# breadboard_rev06.net
KiCad netlist of a schematic drawn in EAGLE
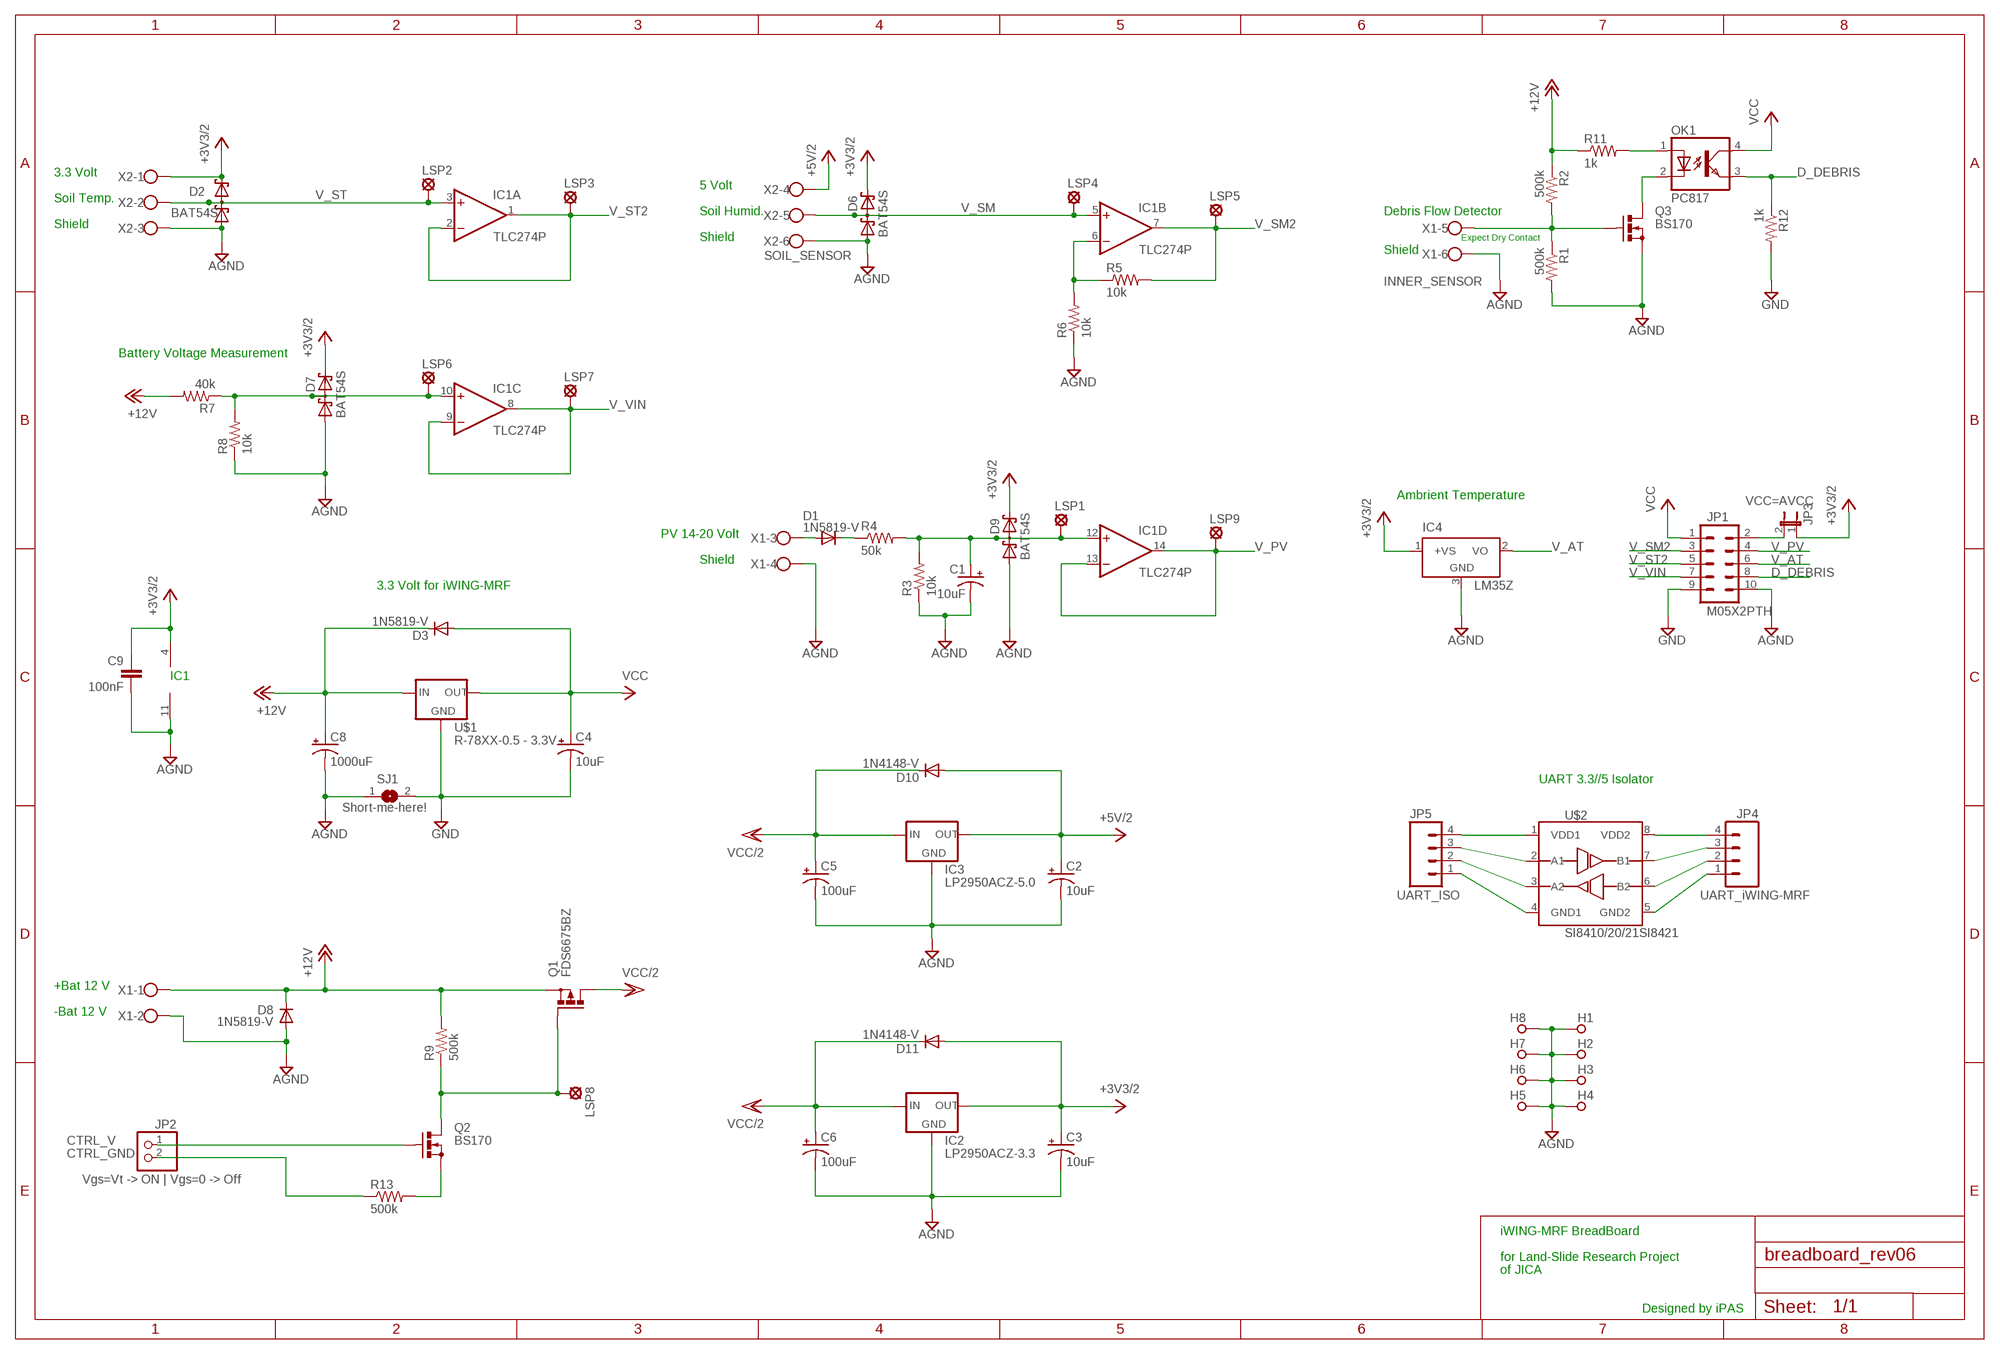
[diagram p0: schematic, sheet 1]

(export (version "E")
  (design (tool "Eeschema 10.0.6"))
  (components
    (comp (ref "C1")
      (value "10uF")
      (footprint "eagle-import:RCL_E2,5-7")
      (libsource (lib "eagle-import") (part "RCL_CPOL-USE2.5-7"))
    )
    (comp (ref "C2")
      (value "10uF")
      (footprint "eagle-import:RCL_E2,5-7")
      (libsource (lib "eagle-import") (part "RCL_CPOL-USE2.5-7"))
    )
    (comp (ref "C3")
      (value "10uF")
      (footprint "eagle-import:RCL_E2,5-7")
      (libsource (lib "eagle-import") (part "RCL_CPOL-USE2.5-7"))
    )
    (comp (ref "C4")
      (value "10uF")
      (footprint "eagle-import:RCL_E2,5-7")
      (libsource (lib "eagle-import") (part "RCL_CPOL-USE2.5-7"))
    )
    (comp (ref "C5")
      (value "100uF")
      (footprint "eagle-import:RCL_E2,5-7")
      (libsource (lib "eagle-import") (part "RCL_CPOL-USE2.5-7"))
    )
    (comp (ref "C6")
      (value "100uF")
      (footprint "eagle-import:RCL_E2,5-7")
      (libsource (lib "eagle-import") (part "RCL_CPOL-USE2.5-7"))
    )
    (comp (ref "C8")
      (value "1000uF")
      (footprint "eagle-import:RCL_E5-13")
      (libsource (lib "eagle-import") (part "RCL_CPOL-USE5-13"))
    )
    (comp (ref "C9")
      (value "100nF")
      (footprint "eagle-import:RCL_C050-025X075")
      (libsource (lib "eagle-import") (part "RCL_C-EU050-025X075"))
    )
    (comp (ref "D1")
      (value "1N5819-V")
      (footprint "eagle-import:DO41-150V")
      (libsource (lib "eagle-import") (part "1N5819-V"))
    )
    (comp (ref "D2")
      (value "BAT54S")
      (footprint "eagle-import:SOT23")
      (libsource (lib "eagle-import") (part "BAT54S"))
    )
    (comp (ref "D3")
      (value "1N5819-V")
      (footprint "eagle-import:DO41-150V")
      (libsource (lib "eagle-import") (part "1N5819-V"))
    )
    (comp (ref "D6")
      (value "BAT54S")
      (footprint "eagle-import:SOT23")
      (libsource (lib "eagle-import") (part "BAT54S"))
    )
    (comp (ref "D7")
      (value "BAT54S")
      (footprint "eagle-import:SOT23")
      (libsource (lib "eagle-import") (part "BAT54S"))
    )
    (comp (ref "D8")
      (value "1N5819-V")
      (footprint "eagle-import:DO41-150V")
      (libsource (lib "eagle-import") (part "1N5819-V"))
    )
    (comp (ref "D9")
      (value "BAT54S")
      (footprint "eagle-import:SOT23")
      (libsource (lib "eagle-import") (part "BAT54S"))
    )
    (comp (ref "D10")
      (value "1N4148-V")
      (footprint "eagle-import:DO35-100V")
      (libsource (lib "eagle-import") (part "1N4148-V"))
    )
    (comp (ref "D11")
      (value "1N4148-V")
      (footprint "eagle-import:DO35-100V")
      (libsource (lib "eagle-import") (part "1N4148-V"))
    )
    (comp (ref "H1")
      (value "SPECIAL_DRILL_0.1560")
      (footprint "eagle-import:PAD_0.1560")
      (libsource (lib "eagle-import") (part "SPECIAL_DRILL_0.1560"))
    )
    (comp (ref "H2")
      (value "SPECIAL_DRILL_0.1560")
      (footprint "eagle-import:PAD_0.1560")
      (libsource (lib "eagle-import") (part "SPECIAL_DRILL_0.1560"))
    )
    (comp (ref "H3")
      (value "SPECIAL_DRILL_0.1560")
      (footprint "eagle-import:PAD_0.1560")
      (libsource (lib "eagle-import") (part "SPECIAL_DRILL_0.1560"))
    )
    (comp (ref "H4")
      (value "SPECIAL_DRILL_0.1560")
      (footprint "eagle-import:PAD_0.1560")
      (libsource (lib "eagle-import") (part "SPECIAL_DRILL_0.1560"))
    )
    (comp (ref "H5")
      (value "SPECIAL_DRILL_0.1560")
      (footprint "eagle-import:PAD_0.1560")
      (libsource (lib "eagle-import") (part "SPECIAL_DRILL_0.1560"))
    )
    (comp (ref "H6")
      (value "SPECIAL_DRILL_0.1560")
      (footprint "eagle-import:PAD_0.1560")
      (libsource (lib "eagle-import") (part "SPECIAL_DRILL_0.1560"))
    )
    (comp (ref "H7")
      (value "SPECIAL_DRILL_0.1560")
      (footprint "eagle-import:PAD_0.1560")
      (libsource (lib "eagle-import") (part "SPECIAL_DRILL_0.1560"))
    )
    (comp (ref "H8")
      (value "SPECIAL_DRILL_0.1560")
      (footprint "eagle-import:PAD_0.1560")
      (libsource (lib "eagle-import") (part "SPECIAL_DRILL_0.1560"))
    )
    (comp (ref "IC1")
      (value "TLC274P")
      (footprint "eagle-import:DIL14")
      (libsource (lib "eagle-import") (part "TLC274P"))
    )
    (comp (ref "IC2")
      (value "LP2950ACZ-3.3")
      (footprint "eagle-import:TO92")
      (libsource (lib "eagle-import") (part "LP2950?ACZ-3.3"))
    )
    (comp (ref "IC3")
      (value "LP2950ACZ-5.0")
      (footprint "eagle-import:TO92")
      (libsource (lib "eagle-import") (part "LP2950?ACZ-5.0"))
    )
    (comp (ref "IC4")
      (value "LM35Z")
      (footprint "eagle-import:TO92")
      (libsource (lib "eagle-import") (part "LM35?Z"))
    )
    (comp (ref "JP1")
      (value "M05X2PTH")
      (footprint "eagle-import:AVR_ICSP")
      (libsource (lib "eagle-import") (part "M05X2PTH"))
    )
    (comp (ref "JP2")
      (value "Vgs=Vt -> ON | Vgs=0 -> Off")
      (footprint "eagle-import:1X02")
      (libsource (lib "eagle-import") (part "PINHD-1X2"))
    )
    (comp (ref "JP3")
      (value "VCC=AVCC")
      (footprint "eagle-import:JUMPER_JP1")
      (libsource (lib "eagle-import") (part "JP1E"))
    )
    (comp (ref "JP4")
      (value "UART_iWING-MRF")
      (footprint "eagle-import:MOLEX-1X4")
      (libsource (lib "eagle-import") (part "M04POLAR"))
    )
    (comp (ref "JP5")
      (value "UART_ISO")
      (footprint "eagle-import:MOLEX-1X4")
      (libsource (lib "eagle-import") (part "M04POLAR"))
    )
    (comp (ref "LSP1")
      (value "LSP13")
      (footprint "eagle-import:LSP13")
      (libsource (lib "eagle-import") (part "LSP13"))
    )
    (comp (ref "LSP2")
      (value "LSP13")
      (footprint "eagle-import:LSP13")
      (libsource (lib "eagle-import") (part "LSP13"))
    )
    (comp (ref "LSP3")
      (value "LSP13")
      (footprint "eagle-import:LSP13")
      (libsource (lib "eagle-import") (part "LSP13"))
    )
    (comp (ref "LSP4")
      (value "LSP13")
      (footprint "eagle-import:LSP13")
      (libsource (lib "eagle-import") (part "LSP13"))
    )
    (comp (ref "LSP5")
      (value "LSP13")
      (footprint "eagle-import:LSP13")
      (libsource (lib "eagle-import") (part "LSP13"))
    )
    (comp (ref "LSP6")
      (value "LSP13")
      (footprint "eagle-import:LSP13")
      (libsource (lib "eagle-import") (part "LSP13"))
    )
    (comp (ref "LSP7")
      (value "LSP13")
      (footprint "eagle-import:LSP13")
      (libsource (lib "eagle-import") (part "LSP13"))
    )
    (comp (ref "LSP8")
      (value "LSP13")
      (footprint "eagle-import:LSP13")
      (libsource (lib "eagle-import") (part "LSP13"))
    )
    (comp (ref "LSP9")
      (value "LSP13")
      (footprint "eagle-import:LSP13")
      (libsource (lib "eagle-import") (part "LSP13"))
    )
    (comp (ref "OK1")
      (value "PC817")
      (footprint "eagle-import:DIL04")
      (fields (field (name "MPN") "PC817X4J000F"))
      (libsource (lib "eagle-import") (part "PC817"))
    )
    (comp (ref "Q1")
      (value "FDS6675BZ")
      (footprint "eagle-import:SO-08")
      (libsource (lib "eagle-import") (part "P-MOSFET-SO8"))
    )
    (comp (ref "Q2")
      (value "BS170")
      (footprint "eagle-import:SOT54E")
      (libsource (lib "eagle-import") (part "BS170"))
    )
    (comp (ref "Q3")
      (value "BS170")
      (footprint "eagle-import:SOT54E")
      (libsource (lib "eagle-import") (part "BS170"))
    )
    (comp (ref "R1")
      (value "500k")
      (footprint "eagle-import:RCL_0204_7")
      (libsource (lib "eagle-import") (part "RCL_R-US_0204/7"))
    )
    (comp (ref "R2")
      (value "500k")
      (footprint "eagle-import:RCL_0204_7")
      (libsource (lib "eagle-import") (part "RCL_R-US_0204/7"))
    )
    (comp (ref "R3")
      (value "10k")
      (footprint "eagle-import:RCL_0204_7")
      (libsource (lib "eagle-import") (part "RCL_R-US_0204/7"))
    )
    (comp (ref "R4")
      (value "50k")
      (footprint "eagle-import:RCL_0204_7")
      (libsource (lib "eagle-import") (part "RCL_R-US_0204/7"))
    )
    (comp (ref "R5")
      (value "10k")
      (footprint "eagle-import:RCL_0204_7")
      (libsource (lib "eagle-import") (part "RCL_R-US_0204/7"))
    )
    (comp (ref "R6")
      (value "10k")
      (footprint "eagle-import:RCL_0204_7")
      (libsource (lib "eagle-import") (part "RCL_R-US_0204/7"))
    )
    (comp (ref "R7")
      (value "40k")
      (footprint "eagle-import:RCL_0204_7")
      (libsource (lib "eagle-import") (part "RCL_R-US_0204/7"))
    )
    (comp (ref "R8")
      (value "10k")
      (footprint "eagle-import:RCL_0204_7")
      (libsource (lib "eagle-import") (part "RCL_R-US_0204/7"))
    )
    (comp (ref "R9")
      (value "500k")
      (footprint "eagle-import:RCL_0204_7")
      (libsource (lib "eagle-import") (part "RCL_R-US_0204/7"))
    )
    (comp (ref "R11")
      (value "1k")
      (footprint "eagle-import:RCL_0204_7")
      (libsource (lib "eagle-import") (part "RCL_R-US_0204/7"))
    )
    (comp (ref "R12")
      (value "1k")
      (footprint "eagle-import:RCL_0204_7")
      (libsource (lib "eagle-import") (part "RCL_R-US_0204/7"))
    )
    (comp (ref "R13")
      (value "500k")
      (footprint "eagle-import:RCL_0204_7")
      (libsource (lib "eagle-import") (part "RCL_R-US_0204/7"))
    )
    (comp (ref "SJ1")
      (value "Short-me-here!")
      (footprint "eagle-import:SJ")
      (libsource (lib "eagle-import") (part "SJ"))
    )
    (comp (ref "U$1")
      (value "R-78XX-0.5 - 3.3V")
      (footprint "eagle-import:SIP3")
      (libsource (lib "eagle-import") (part "R-78XX-0.5"))
    )
    (comp (ref "U$2")
      (value "SI8410/20/21SI8421")
      (footprint "eagle-import:SO-08")
      (libsource (lib "eagle-import") (part "SI8410/20/21SI8421"))
    )
    (comp (ref "X1")
      (value "INNER_SENSOR")
      (footprint "eagle-import:5EHDRC-6P")
      (libsource (lib "eagle-import") (part "5EHDRC-6P"))
    )
    (comp (ref "X2")
      (value "SOIL_SENSOR")
      (footprint "eagle-import:5EHDRC-6P")
      (libsource (lib "eagle-import") (part "5EHDRC-6P"))
    )
  )
  (nets
    (net (code "1") (name "+3V3{slash}2") (class "Default")
      (node (ref "C3") (pin "+") (pinfunction "+_+") (pintype "passive"))
      (node (ref "C9") (pin "1") (pinfunction "1_1") (pintype "passive"))
      (node (ref "D11") (pin "A") (pinfunction "A_A") (pintype "passive"))
      (node (ref "D2") (pin "2") (pinfunction "C2_2") (pintype "passive"))
      (node (ref "D6") (pin "2") (pinfunction "C2_2") (pintype "passive"))
      (node (ref "D7") (pin "2") (pinfunction "C2_2") (pintype "passive"))
      (node (ref "D9") (pin "2") (pinfunction "C2_2") (pintype "passive"))
      (node (ref "IC1") (pin "4") (pinfunction "V+_4") (pintype "power_in"))
      (node (ref "IC2") (pin "1") (pinfunction "OUT_1") (pintype "passive"))
      (node (ref "IC4") (pin "1") (pinfunction "+VS_1") (pintype "input"))
      (node (ref "JP3") (pin "1") (pinfunction "1_1") (pintype "passive"))
      (node (ref "X2") (pin "1") (pinfunction "KL_1") (pintype "passive"))
    )
    (net (code "2") (name "+5V{slash}2") (class "Default")
      (node (ref "C2") (pin "+") (pinfunction "+_+") (pintype "passive"))
      (node (ref "D10") (pin "A") (pinfunction "A_A") (pintype "passive"))
      (node (ref "IC3") (pin "1") (pinfunction "OUT_1") (pintype "passive"))
      (node (ref "X2") (pin "4") (pinfunction "KL_4") (pintype "passive"))
    )
    (net (code "3") (name "+12V") (class "Default")
      (node (ref "C8") (pin "+") (pinfunction "+_+") (pintype "passive"))
      (node (ref "D3") (pin "C") (pinfunction "C_C") (pintype "passive"))
      (node (ref "D8") (pin "C") (pinfunction "C_C") (pintype "passive"))
      (node (ref "Q1") (pin "1") (pinfunction "S_1") (pintype "passive"))
      (node (ref "Q1") (pin "2") (pinfunction "S_2") (pintype "passive"))
      (node (ref "Q1") (pin "3") (pinfunction "S_3") (pintype "passive"))
      (node (ref "R11") (pin "1") (pinfunction "1_1") (pintype "passive"))
      (node (ref "R2") (pin "1") (pinfunction "1_1") (pintype "passive"))
      (node (ref "R7") (pin "2") (pinfunction "2_2") (pintype "passive"))
      (node (ref "R9") (pin "2") (pinfunction "2_2") (pintype "passive"))
      (node (ref "U$1") (pin "1") (pinfunction "IN_1") (pintype "input"))
      (node (ref "X1") (pin "1") (pinfunction "KL_1") (pintype "passive"))
    )
    (net (code "4") (name "/CTRL_GND") (class "Default")
      (node (ref "JP2") (pin "2") (pinfunction "2_2") (pintype "passive"))
      (node (ref "R13") (pin "1") (pinfunction "1_1") (pintype "passive"))
    )
    (net (code "5") (name "/CTRL_V") (class "Default")
      (node (ref "JP2") (pin "1") (pinfunction "1_1") (pintype "passive"))
      (node (ref "Q2") (pin "G") (pinfunction "G_G") (pintype "passive"))
    )
    (net (code "6") (name "/D_DEBRIS") (class "Default")
      (node (ref "JP1") (pin "8") (pinfunction "8_8") (pintype "passive"))
      (node (ref "OK1") (pin "3") (pinfunction "EMIT_3") (pintype "passive"))
      (node (ref "R12") (pin "1") (pinfunction "1_1") (pintype "passive"))
    )
    (net (code "7") (name "/V_AT") (class "Default")
      (node (ref "IC4") (pin "2") (pinfunction "VO_2") (pintype "output"))
      (node (ref "JP1") (pin "6") (pinfunction "6_6") (pintype "passive"))
    )
    (net (code "8") (name "/V_PV") (class "Default")
      (node (ref "IC1") (pin "13") (pinfunction "-IN_13") (pintype "input"))
      (node (ref "IC1") (pin "14") (pinfunction "OUT_14") (pintype "output"))
      (node (ref "JP1") (pin "4") (pinfunction "4_4") (pintype "passive"))
      (node (ref "LSP9") (pin "MP") (pinfunction "MP_MP") (pintype "passive"))
    )
    (net (code "9") (name "/V_SM") (class "Default")
      (node (ref "D6") (pin "3") (pinfunction "C1A2_3") (pintype "passive"))
      (node (ref "IC1") (pin "5") (pinfunction "+IN_5") (pintype "input"))
      (node (ref "LSP4") (pin "MP") (pinfunction "MP_MP") (pintype "passive"))
      (node (ref "X2") (pin "5") (pinfunction "KL_5") (pintype "passive"))
    )
    (net (code "10") (name "/V_SM2") (class "Default")
      (node (ref "IC1") (pin "7") (pinfunction "OUT_7") (pintype "output"))
      (node (ref "JP1") (pin "3") (pinfunction "3_3") (pintype "passive"))
      (node (ref "LSP5") (pin "MP") (pinfunction "MP_MP") (pintype "passive"))
      (node (ref "R5") (pin "2") (pinfunction "2_2") (pintype "passive"))
    )
    (net (code "11") (name "/V_ST") (class "Default")
      (node (ref "D2") (pin "3") (pinfunction "C1A2_3") (pintype "passive"))
      (node (ref "IC1") (pin "3") (pinfunction "+IN_3") (pintype "input"))
      (node (ref "LSP2") (pin "MP") (pinfunction "MP_MP") (pintype "passive"))
      (node (ref "X2") (pin "2") (pinfunction "KL_2") (pintype "passive"))
    )
    (net (code "12") (name "/V_ST2") (class "Default")
      (node (ref "IC1") (pin "1") (pinfunction "OUT_1") (pintype "output"))
      (node (ref "IC1") (pin "2") (pinfunction "-IN_2") (pintype "input"))
      (node (ref "JP1") (pin "5") (pinfunction "5_5") (pintype "passive"))
      (node (ref "LSP3") (pin "MP") (pinfunction "MP_MP") (pintype "passive"))
    )
    (net (code "13") (name "/V_VIN") (class "Default")
      (node (ref "IC1") (pin "8") (pinfunction "OUT_8") (pintype "output"))
      (node (ref "IC1") (pin "9") (pinfunction "-IN_9") (pintype "input"))
      (node (ref "JP1") (pin "7") (pinfunction "7_7") (pintype "passive"))
      (node (ref "LSP7") (pin "MP") (pinfunction "MP_MP") (pintype "passive"))
    )
    (net (code "14") (name "AGND") (class "Default")
      (node (ref "C1") (pin "-") (pinfunction "-_-") (pintype "passive"))
      (node (ref "C2") (pin "-") (pinfunction "-_-") (pintype "passive"))
      (node (ref "C3") (pin "-") (pinfunction "-_-") (pintype "passive"))
      (node (ref "C5") (pin "-") (pinfunction "-_-") (pintype "passive"))
      (node (ref "C6") (pin "-") (pinfunction "-_-") (pintype "passive"))
      (node (ref "C8") (pin "-") (pinfunction "-_-") (pintype "passive"))
      (node (ref "C9") (pin "2") (pinfunction "2_2") (pintype "passive"))
      (node (ref "D2") (pin "1") (pinfunction "A1_1") (pintype "passive"))
      (node (ref "D6") (pin "1") (pinfunction "A1_1") (pintype "passive"))
      (node (ref "D7") (pin "1") (pinfunction "A1_1") (pintype "passive"))
      (node (ref "D8") (pin "A") (pinfunction "A_A") (pintype "passive"))
      (node (ref "D9") (pin "1") (pinfunction "A1_1") (pintype "passive"))
      (node (ref "H1") (pin "1") (pinfunction "1_1") (pintype "passive"))
      (node (ref "H2") (pin "1") (pinfunction "1_1") (pintype "passive"))
      (node (ref "H3") (pin "1") (pinfunction "1_1") (pintype "passive"))
      (node (ref "H4") (pin "1") (pinfunction "1_1") (pintype "passive"))
      (node (ref "H5") (pin "1") (pinfunction "1_1") (pintype "passive"))
      (node (ref "H6") (pin "1") (pinfunction "1_1") (pintype "passive"))
      (node (ref "H7") (pin "1") (pinfunction "1_1") (pintype "passive"))
      (node (ref "H8") (pin "1") (pinfunction "1_1") (pintype "passive"))
      (node (ref "IC1") (pin "11") (pinfunction "V-_11") (pintype "power_in"))
      (node (ref "IC2") (pin "2") (pinfunction "GND_2") (pintype "input"))
      (node (ref "IC3") (pin "2") (pinfunction "GND_2") (pintype "input"))
      (node (ref "IC4") (pin "3") (pinfunction "GND_3") (pintype "power_in"))
      (node (ref "JP1") (pin "10") (pinfunction "10_10") (pintype "passive"))
      (node (ref "Q3") (pin "S") (pinfunction "S_S") (pintype "passive"))
      (node (ref "R1") (pin "2") (pinfunction "2_2") (pintype "passive"))
      (node (ref "R3") (pin "1") (pinfunction "1_1") (pintype "passive"))
      (node (ref "R6") (pin "1") (pinfunction "1_1") (pintype "passive"))
      (node (ref "R8") (pin "1") (pinfunction "1_1") (pintype "passive"))
      (node (ref "SJ1") (pin "1") (pinfunction "1_1") (pintype "passive"))
      (node (ref "X1") (pin "2") (pinfunction "KL_2") (pintype "passive"))
      (node (ref "X1") (pin "4") (pinfunction "KL_4") (pintype "passive"))
      (node (ref "X1") (pin "6") (pinfunction "KL_6") (pintype "passive"))
      (node (ref "X2") (pin "3") (pinfunction "KL_3") (pintype "passive"))
      (node (ref "X2") (pin "6") (pinfunction "KL_6") (pintype "passive"))
    )
    (net (code "15") (name "GND") (class "Default")
      (node (ref "C4") (pin "-") (pinfunction "-_-") (pintype "passive"))
      (node (ref "JP1") (pin "9") (pinfunction "9_9") (pintype "passive"))
      (node (ref "R12") (pin "2") (pinfunction "2_2") (pintype "passive"))
      (node (ref "SJ1") (pin "2") (pinfunction "2_2") (pintype "passive"))
      (node (ref "U$1") (pin "2") (pinfunction "GND_2") (pintype "input"))
    )
    (net (code "16") (name "Net-(D1-PadC)") (class "Default")
      (node (ref "D1") (pin "C") (pinfunction "C_C") (pintype "passive"))
      (node (ref "R4") (pin "1") (pinfunction "1_1") (pintype "passive"))
    )
    (net (code "17") (name "Net-(D7-C1A2)") (class "Default")
      (node (ref "D7") (pin "3") (pinfunction "C1A2_3") (pintype "passive"))
      (node (ref "IC1") (pin "10") (pinfunction "+IN_10") (pintype "input"))
      (node (ref "LSP6") (pin "MP") (pinfunction "MP_MP") (pintype "passive"))
      (node (ref "R7") (pin "1") (pinfunction "1_1") (pintype "passive"))
      (node (ref "R8") (pin "2") (pinfunction "2_2") (pintype "passive"))
    )
    (net (code "18") (name "Net-(D9-C1A2)") (class "Default")
      (node (ref "C1") (pin "+") (pinfunction "+_+") (pintype "passive"))
      (node (ref "D9") (pin "3") (pinfunction "C1A2_3") (pintype "passive"))
      (node (ref "IC1") (pin "12") (pinfunction "+IN_12") (pintype "input"))
      (node (ref "LSP1") (pin "MP") (pinfunction "MP_MP") (pintype "passive"))
      (node (ref "R3") (pin "2") (pinfunction "2_2") (pintype "passive"))
      (node (ref "R4") (pin "2") (pinfunction "2_2") (pintype "passive"))
    )
    (net (code "19") (name "Net-(IC1B--IN)") (class "Default")
      (node (ref "IC1") (pin "6") (pinfunction "-IN_6") (pintype "input"))
      (node (ref "R5") (pin "1") (pinfunction "1_1") (pintype "passive"))
      (node (ref "R6") (pin "2") (pinfunction "2_2") (pintype "passive"))
    )
    (net (code "20") (name "Net-(JP1-Pad2)") (class "Default")
      (node (ref "JP1") (pin "2") (pinfunction "2_2") (pintype "passive"))
      (node (ref "JP3") (pin "2") (pinfunction "2_2") (pintype "passive"))
    )
    (net (code "21") (name "Net-(OK1-A)") (class "Default")
      (node (ref "OK1") (pin "1") (pinfunction "A_1") (pintype "passive"))
      (node (ref "R11") (pin "2") (pinfunction "2_2") (pintype "passive"))
    )
    (net (code "22") (name "Net-(OK1-C)") (class "Default")
      (node (ref "OK1") (pin "2") (pinfunction "C_2") (pintype "passive"))
      (node (ref "Q3") (pin "D") (pinfunction "D_D") (pintype "passive"))
    )
    (net (code "23") (name "Net-(Q1-G)") (class "Default")
      (node (ref "LSP8") (pin "MP") (pinfunction "MP_MP") (pintype "passive"))
      (node (ref "Q1") (pin "4") (pinfunction "G_4") (pintype "passive"))
      (node (ref "Q2") (pin "D") (pinfunction "D_D") (pintype "passive"))
      (node (ref "R9") (pin "1") (pinfunction "1_1") (pintype "passive"))
    )
    (net (code "24") (name "Net-(Q2-PadS)") (class "Default")
      (node (ref "Q2") (pin "S") (pinfunction "S_S") (pintype "passive"))
      (node (ref "R13") (pin "2") (pinfunction "2_2") (pintype "passive"))
    )
    (net (code "25") (name "Net-(U$2-A1)") (class "Default")
      (node (ref "JP5") (pin "3") (pinfunction "3_3") (pintype "passive"))
      (node (ref "U$2") (pin "2") (pinfunction "A1_2") (pintype "input"))
    )
    (net (code "26") (name "Net-(U$2-A2)") (class "Default")
      (node (ref "JP5") (pin "2") (pinfunction "2_2") (pintype "passive"))
      (node (ref "U$2") (pin "3") (pinfunction "A2_3") (pintype "output"))
    )
    (net (code "27") (name "Net-(U$2-B1)") (class "Default")
      (node (ref "JP4") (pin "3") (pinfunction "3_3") (pintype "passive"))
      (node (ref "U$2") (pin "7") (pinfunction "B1_7") (pintype "output"))
    )
    (net (code "28") (name "Net-(U$2-B2)") (class "Default")
      (node (ref "JP4") (pin "2") (pinfunction "2_2") (pintype "passive"))
      (node (ref "U$2") (pin "6") (pinfunction "B2_6") (pintype "input"))
    )
    (net (code "29") (name "Net-(U$2-GND1)") (class "Default")
      (node (ref "JP5") (pin "1") (pinfunction "1_1") (pintype "passive"))
      (node (ref "U$2") (pin "4") (pinfunction "GND1_4") (pintype "power_in"))
    )
    (net (code "30") (name "Net-(U$2-GND2)") (class "Default")
      (node (ref "JP4") (pin "1") (pinfunction "1_1") (pintype "passive"))
      (node (ref "U$2") (pin "5") (pinfunction "GND2_5") (pintype "power_in"))
    )
    (net (code "31") (name "Net-(U$2-VDD1)") (class "Default")
      (node (ref "JP5") (pin "4") (pinfunction "4_4") (pintype "passive"))
      (node (ref "U$2") (pin "1") (pinfunction "VDD1_1") (pintype "power_in"))
    )
    (net (code "32") (name "Net-(U$2-VDD2)") (class "Default")
      (node (ref "JP4") (pin "4") (pinfunction "4_4") (pintype "passive"))
      (node (ref "U$2") (pin "8") (pinfunction "VDD2_8") (pintype "power_in"))
    )
    (net (code "33") (name "Net-(X1C-KL)") (class "Default")
      (node (ref "D1") (pin "A") (pinfunction "A_A") (pintype "passive"))
      (node (ref "X1") (pin "3") (pinfunction "KL_3") (pintype "passive"))
    )
    (net (code "34") (name "Net-(X1E-KL)") (class "Default")
      (node (ref "Q3") (pin "G") (pinfunction "G_G") (pintype "passive"))
      (node (ref "R1") (pin "1") (pinfunction "1_1") (pintype "passive"))
      (node (ref "R2") (pin "2") (pinfunction "2_2") (pintype "passive"))
      (node (ref "X1") (pin "5") (pinfunction "KL_5") (pintype "passive"))
    )
    (net (code "35") (name "VCC") (class "Default")
      (node (ref "C4") (pin "+") (pinfunction "+_+") (pintype "passive"))
      (node (ref "D3") (pin "A") (pinfunction "A_A") (pintype "passive"))
      (node (ref "JP1") (pin "1") (pinfunction "1_1") (pintype "passive"))
      (node (ref "OK1") (pin "4") (pinfunction "COL_4") (pintype "passive"))
      (node (ref "U$1") (pin "3") (pinfunction "OUT_3") (pintype "passive"))
    )
    (net (code "36") (name "VCC{slash}2") (class "Default")
      (node (ref "C5") (pin "+") (pinfunction "+_+") (pintype "passive"))
      (node (ref "C6") (pin "+") (pinfunction "+_+") (pintype "passive"))
      (node (ref "D10") (pin "C") (pinfunction "C_C") (pintype "passive"))
      (node (ref "D11") (pin "C") (pinfunction "C_C") (pintype "passive"))
      (node (ref "IC2") (pin "3") (pinfunction "IN_3") (pintype "input"))
      (node (ref "IC3") (pin "3") (pinfunction "IN_3") (pintype "input"))
      (node (ref "Q1") (pin "5") (pinfunction "D_5") (pintype "passive"))
      (node (ref "Q1") (pin "6") (pinfunction "D_6") (pintype "passive"))
      (node (ref "Q1") (pin "7") (pinfunction "D_7") (pintype "passive"))
      (node (ref "Q1") (pin "8") (pinfunction "D_8") (pintype "passive"))
    )
  )
)
